# Sheet1.net
KiCad netlist of a schematic drawn in Altium Designer
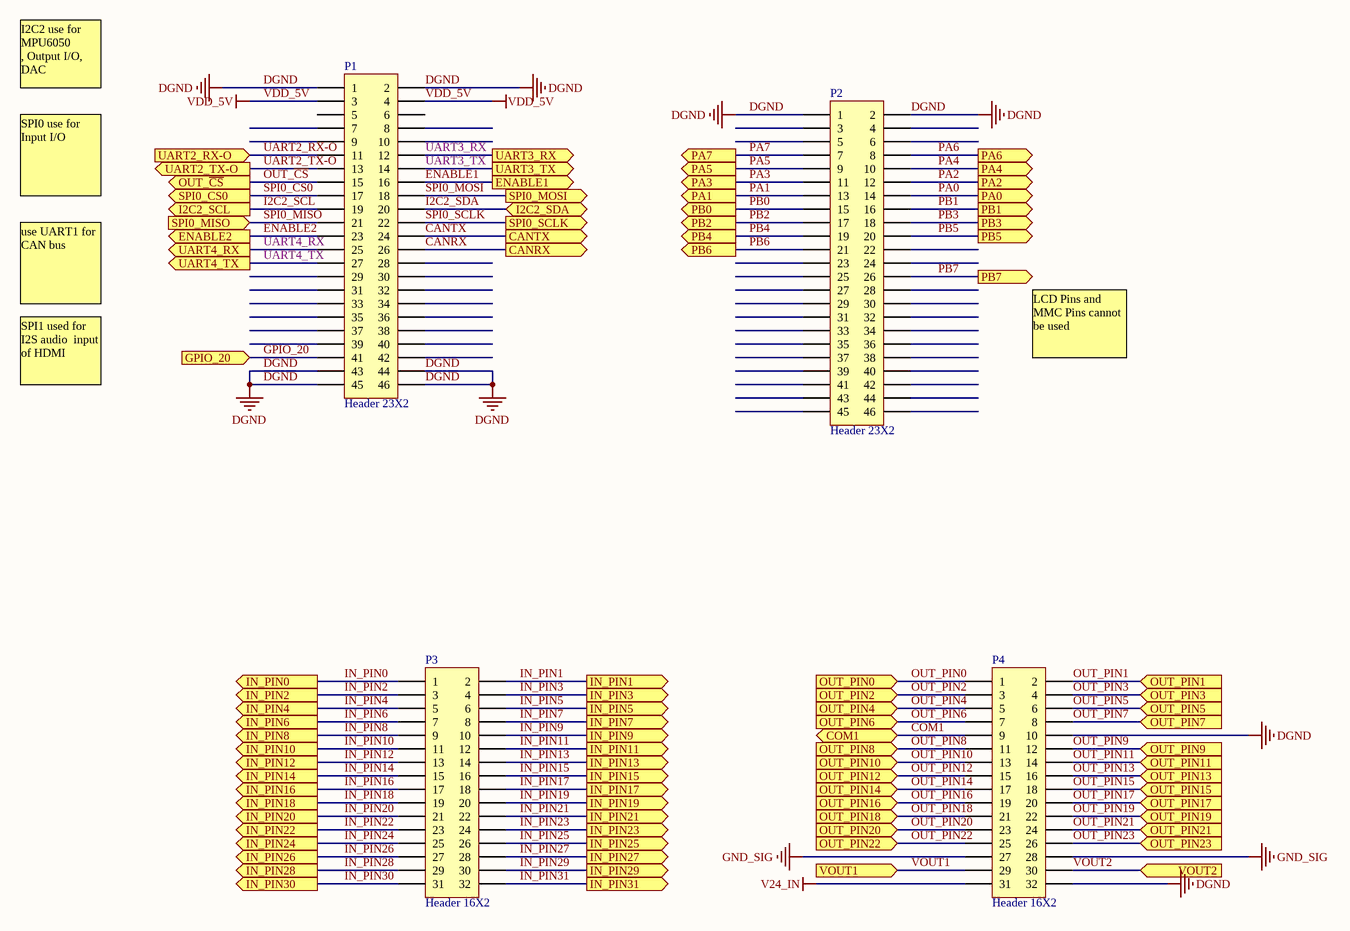
[diagram p0: Sheet1.SchDoc]

(export (version "E")
  (design (tool "Eeschema 10.0.6"))
  (components
    (comp (ref "P1")
      (value "Header 23X2")
      (footprint "HDR2X23")
      (description "Header, 23-Pin, Dual row")
      (fields (field (name "PUBLISHER") "Altium Limited"))
      (libsource (lib "dolphi_ecs") (part "Header 23X2"))
    )
    (comp (ref "P2")
      (value "Header 23X2")
      (footprint "HDR2X23")
      (description "Header, 23-Pin, Dual row")
      (fields (field (name "PUBLISHER") "Altium Limited"))
      (libsource (lib "dolphi_ecs") (part "Header 23X2"))
    )
    (comp (ref "P3")
      (value "Header 16X2")
      (footprint "CON16X2-8.5")
      (description "Header, 16-Pin, Dual row")
      (fields (field (name "PUBLISHER") "Altium Limited"))
      (libsource (lib "Miscellaneous Connectors") (part "Header 16X2"))
    )
    (comp (ref "P4")
      (value "Header 16X2")
      (footprint "CON16X2-8.5")
      (description "Header, 16-Pin, Dual row")
      (fields (field (name "PUBLISHER") "Altium Limited"))
      (libsource (lib "Miscellaneous Connectors") (part "Header 16X2"))
    )
  )
  (nets
    (net (code "1") (name "/CANRX") (class "Default")
      (node (ref "P1") (pin "26") (pinfunction "26_26") (pintype "passive"))
    )
    (net (code "2") (name "/CANTX") (class "Default")
      (node (ref "P1") (pin "24") (pinfunction "24_24") (pintype "passive"))
    )
    (net (code "3") (name "/COM1") (class "Default")
      (node (ref "P4") (pin "9") (pinfunction "9_9") (pintype "passive"))
    )
    (net (code "4") (name "/ENABLE1") (class "Default")
      (node (ref "P1") (pin "16") (pinfunction "16_16") (pintype "passive"))
    )
    (net (code "5") (name "/ENABLE2") (class "Default")
      (node (ref "P1") (pin "23") (pinfunction "23_23") (pintype "passive"))
    )
    (net (code "6") (name "/GPIO_20") (class "Default")
      (node (ref "P1") (pin "41") (pinfunction "41_41") (pintype "passive"))
    )
    (net (code "7") (name "/I2C2_SCL") (class "Default")
      (node (ref "P1") (pin "19") (pinfunction "19_19") (pintype "passive"))
    )
    (net (code "8") (name "/I2C2_SDA") (class "Default")
      (node (ref "P1") (pin "20") (pinfunction "20_20") (pintype "passive"))
    )
    (net (code "9") (name "/IN_PIN0") (class "Default")
      (node (ref "P3") (pin "1") (pinfunction "1_1") (pintype "passive"))
    )
    (net (code "10") (name "/IN_PIN1") (class "Default")
      (node (ref "P3") (pin "2") (pinfunction "2_2") (pintype "passive"))
    )
    (net (code "11") (name "/IN_PIN2") (class "Default")
      (node (ref "P3") (pin "3") (pinfunction "3_3") (pintype "passive"))
    )
    (net (code "12") (name "/IN_PIN3") (class "Default")
      (node (ref "P3") (pin "4") (pinfunction "4_4") (pintype "passive"))
    )
    (net (code "13") (name "/IN_PIN4") (class "Default")
      (node (ref "P3") (pin "5") (pinfunction "5_5") (pintype "passive"))
    )
    (net (code "14") (name "/IN_PIN5") (class "Default")
      (node (ref "P3") (pin "6") (pinfunction "6_6") (pintype "passive"))
    )
    (net (code "15") (name "/IN_PIN6") (class "Default")
      (node (ref "P3") (pin "7") (pinfunction "7_7") (pintype "passive"))
    )
    (net (code "16") (name "/IN_PIN7") (class "Default")
      (node (ref "P3") (pin "8") (pinfunction "8_8") (pintype "passive"))
    )
    (net (code "17") (name "/IN_PIN8") (class "Default")
      (node (ref "P3") (pin "9") (pinfunction "9_9") (pintype "passive"))
    )
    (net (code "18") (name "/IN_PIN9") (class "Default")
      (node (ref "P3") (pin "10") (pinfunction "10_10") (pintype "passive"))
    )
    (net (code "19") (name "/IN_PIN10") (class "Default")
      (node (ref "P3") (pin "11") (pinfunction "11_11") (pintype "passive"))
    )
    (net (code "20") (name "/IN_PIN11") (class "Default")
      (node (ref "P3") (pin "12") (pinfunction "12_12") (pintype "passive"))
    )
    (net (code "21") (name "/IN_PIN12") (class "Default")
      (node (ref "P3") (pin "13") (pinfunction "13_13") (pintype "passive"))
    )
    (net (code "22") (name "/IN_PIN13") (class "Default")
      (node (ref "P3") (pin "14") (pinfunction "14_14") (pintype "passive"))
    )
    (net (code "23") (name "/IN_PIN14") (class "Default")
      (node (ref "P3") (pin "15") (pinfunction "15_15") (pintype "passive"))
    )
    (net (code "24") (name "/IN_PIN15") (class "Default")
      (node (ref "P3") (pin "16") (pinfunction "16_16") (pintype "passive"))
    )
    (net (code "25") (name "/IN_PIN16") (class "Default")
      (node (ref "P3") (pin "17") (pinfunction "17_17") (pintype "passive"))
    )
    (net (code "26") (name "/IN_PIN17") (class "Default")
      (node (ref "P3") (pin "18") (pinfunction "18_18") (pintype "passive"))
    )
    (net (code "27") (name "/IN_PIN18") (class "Default")
      (node (ref "P3") (pin "19") (pinfunction "19_19") (pintype "passive"))
    )
    (net (code "28") (name "/IN_PIN19") (class "Default")
      (node (ref "P3") (pin "20") (pinfunction "20_20") (pintype "passive"))
    )
    (net (code "29") (name "/IN_PIN20") (class "Default")
      (node (ref "P3") (pin "21") (pinfunction "21_21") (pintype "passive"))
    )
    (net (code "30") (name "/IN_PIN21") (class "Default")
      (node (ref "P3") (pin "22") (pinfunction "22_22") (pintype "passive"))
    )
    (net (code "31") (name "/IN_PIN22") (class "Default")
      (node (ref "P3") (pin "23") (pinfunction "23_23") (pintype "passive"))
    )
    (net (code "32") (name "/IN_PIN23") (class "Default")
      (node (ref "P3") (pin "24") (pinfunction "24_24") (pintype "passive"))
    )
    (net (code "33") (name "/IN_PIN24") (class "Default")
      (node (ref "P3") (pin "25") (pinfunction "25_25") (pintype "passive"))
    )
    (net (code "34") (name "/IN_PIN25") (class "Default")
      (node (ref "P3") (pin "26") (pinfunction "26_26") (pintype "passive"))
    )
    (net (code "35") (name "/IN_PIN26") (class "Default")
      (node (ref "P3") (pin "27") (pinfunction "27_27") (pintype "passive"))
    )
    (net (code "36") (name "/IN_PIN27") (class "Default")
      (node (ref "P3") (pin "28") (pinfunction "28_28") (pintype "passive"))
    )
    (net (code "37") (name "/IN_PIN28") (class "Default")
      (node (ref "P3") (pin "29") (pinfunction "29_29") (pintype "passive"))
    )
    (net (code "38") (name "/IN_PIN29") (class "Default")
      (node (ref "P3") (pin "30") (pinfunction "30_30") (pintype "passive"))
    )
    (net (code "39") (name "/IN_PIN30") (class "Default")
      (node (ref "P3") (pin "31") (pinfunction "31_31") (pintype "passive"))
    )
    (net (code "40") (name "/IN_PIN31") (class "Default")
      (node (ref "P3") (pin "32") (pinfunction "32_32") (pintype "passive"))
    )
    (net (code "41") (name "/OUT_PIN0") (class "Default")
      (node (ref "P4") (pin "1") (pinfunction "1_1") (pintype "passive"))
    )
    (net (code "42") (name "/OUT_PIN1") (class "Default")
      (node (ref "P4") (pin "2") (pinfunction "2_2") (pintype "passive"))
    )
    (net (code "43") (name "/OUT_PIN2") (class "Default")
      (node (ref "P4") (pin "3") (pinfunction "3_3") (pintype "passive"))
    )
    (net (code "44") (name "/OUT_PIN3") (class "Default")
      (node (ref "P4") (pin "4") (pinfunction "4_4") (pintype "passive"))
    )
    (net (code "45") (name "/OUT_PIN4") (class "Default")
      (node (ref "P4") (pin "5") (pinfunction "5_5") (pintype "passive"))
    )
    (net (code "46") (name "/OUT_PIN5") (class "Default")
      (node (ref "P4") (pin "6") (pinfunction "6_6") (pintype "passive"))
    )
    (net (code "47") (name "/OUT_PIN6") (class "Default")
      (node (ref "P4") (pin "7") (pinfunction "7_7") (pintype "passive"))
    )
    (net (code "48") (name "/OUT_PIN7") (class "Default")
      (node (ref "P4") (pin "8") (pinfunction "8_8") (pintype "passive"))
    )
    (net (code "49") (name "/OUT_PIN8") (class "Default")
      (node (ref "P4") (pin "11") (pinfunction "11_11") (pintype "passive"))
    )
    (net (code "50") (name "/OUT_PIN9") (class "Default")
      (node (ref "P4") (pin "12") (pinfunction "12_12") (pintype "passive"))
    )
    (net (code "51") (name "/OUT_PIN10") (class "Default")
      (node (ref "P4") (pin "13") (pinfunction "13_13") (pintype "passive"))
    )
    (net (code "52") (name "/OUT_PIN11") (class "Default")
      (node (ref "P4") (pin "14") (pinfunction "14_14") (pintype "passive"))
    )
    (net (code "53") (name "/OUT_PIN12") (class "Default")
      (node (ref "P4") (pin "15") (pinfunction "15_15") (pintype "passive"))
    )
    (net (code "54") (name "/OUT_PIN13") (class "Default")
      (node (ref "P4") (pin "16") (pinfunction "16_16") (pintype "passive"))
    )
    (net (code "55") (name "/OUT_PIN14") (class "Default")
      (node (ref "P4") (pin "17") (pinfunction "17_17") (pintype "passive"))
    )
    (net (code "56") (name "/OUT_PIN15") (class "Default")
      (node (ref "P4") (pin "18") (pinfunction "18_18") (pintype "passive"))
    )
    (net (code "57") (name "/OUT_PIN16") (class "Default")
      (node (ref "P4") (pin "19") (pinfunction "19_19") (pintype "passive"))
    )
    (net (code "58") (name "/OUT_PIN17") (class "Default")
      (node (ref "P4") (pin "20") (pinfunction "20_20") (pintype "passive"))
    )
    (net (code "59") (name "/OUT_PIN18") (class "Default")
      (node (ref "P4") (pin "21") (pinfunction "21_21") (pintype "passive"))
    )
    (net (code "60") (name "/OUT_PIN19") (class "Default")
      (node (ref "P4") (pin "22") (pinfunction "22_22") (pintype "passive"))
    )
    (net (code "61") (name "/OUT_PIN20") (class "Default")
      (node (ref "P4") (pin "23") (pinfunction "23_23") (pintype "passive"))
    )
    (net (code "62") (name "/OUT_PIN21") (class "Default")
      (node (ref "P4") (pin "24") (pinfunction "24_24") (pintype "passive"))
    )
    (net (code "63") (name "/OUT_PIN22") (class "Default")
      (node (ref "P4") (pin "25") (pinfunction "25_25") (pintype "passive"))
    )
    (net (code "64") (name "/OUT_PIN23") (class "Default")
      (node (ref "P4") (pin "26") (pinfunction "26_26") (pintype "passive"))
    )
    (net (code "65") (name "/OUT_~{CS}") (class "Default")
      (node (ref "P1") (pin "15") (pinfunction "15_15") (pintype "passive"))
    )
    (net (code "66") (name "/PA0") (class "Default")
      (node (ref "P2") (pin "14") (pinfunction "14_14") (pintype "passive"))
    )
    (net (code "67") (name "/PA1") (class "Default")
      (node (ref "P2") (pin "13") (pinfunction "13_13") (pintype "passive"))
    )
    (net (code "68") (name "/PA2") (class "Default")
      (node (ref "P2") (pin "12") (pinfunction "12_12") (pintype "passive"))
    )
    (net (code "69") (name "/PA3") (class "Default")
      (node (ref "P2") (pin "11") (pinfunction "11_11") (pintype "passive"))
    )
    (net (code "70") (name "/PA4") (class "Default")
      (node (ref "P2") (pin "10") (pinfunction "10_10") (pintype "passive"))
    )
    (net (code "71") (name "/PA5") (class "Default")
      (node (ref "P2") (pin "9") (pinfunction "9_9") (pintype "passive"))
    )
    (net (code "72") (name "/PA6") (class "Default")
      (node (ref "P2") (pin "8") (pinfunction "8_8") (pintype "passive"))
    )
    (net (code "73") (name "/PA7") (class "Default")
      (node (ref "P2") (pin "7") (pinfunction "7_7") (pintype "passive"))
    )
    (net (code "74") (name "/PB0") (class "Default")
      (node (ref "P2") (pin "15") (pinfunction "15_15") (pintype "passive"))
    )
    (net (code "75") (name "/PB1") (class "Default")
      (node (ref "P2") (pin "16") (pinfunction "16_16") (pintype "passive"))
    )
    (net (code "76") (name "/PB2") (class "Default")
      (node (ref "P2") (pin "17") (pinfunction "17_17") (pintype "passive"))
    )
    (net (code "77") (name "/PB3") (class "Default")
      (node (ref "P2") (pin "18") (pinfunction "18_18") (pintype "passive"))
    )
    (net (code "78") (name "/PB4") (class "Default")
      (node (ref "P2") (pin "19") (pinfunction "19_19") (pintype "passive"))
    )
    (net (code "79") (name "/PB5") (class "Default")
      (node (ref "P2") (pin "20") (pinfunction "20_20") (pintype "passive"))
    )
    (net (code "80") (name "/PB6") (class "Default")
      (node (ref "P2") (pin "21") (pinfunction "21_21") (pintype "passive"))
    )
    (net (code "81") (name "/PB7") (class "Default")
      (node (ref "P2") (pin "26") (pinfunction "26_26") (pintype "passive"))
    )
    (net (code "82") (name "/SPI0_CS0") (class "Default")
      (node (ref "P1") (pin "17") (pinfunction "17_17") (pintype "passive"))
    )
    (net (code "83") (name "/SPI0_MISO") (class "Default")
      (node (ref "P1") (pin "21") (pinfunction "21_21") (pintype "passive"))
    )
    (net (code "84") (name "/SPI0_MOSI") (class "Default")
      (node (ref "P1") (pin "18") (pinfunction "18_18") (pintype "passive"))
    )
    (net (code "85") (name "/SPI0_SCLK") (class "Default")
      (node (ref "P1") (pin "22") (pinfunction "22_22") (pintype "passive"))
    )
    (net (code "86") (name "/UART2_RX-O") (class "Default")
      (node (ref "P1") (pin "11") (pinfunction "11_11") (pintype "passive"))
    )
    (net (code "87") (name "/UART2_TX-O") (class "Default")
      (node (ref "P1") (pin "13") (pinfunction "13_13") (pintype "passive"))
    )
    (net (code "88") (name "/UART3_RX") (class "Default")
      (node (ref "P1") (pin "12") (pinfunction "12_12") (pintype "passive"))
    )
    (net (code "89") (name "/UART3_TX") (class "Default")
      (node (ref "P1") (pin "14") (pinfunction "14_14") (pintype "passive"))
    )
    (net (code "90") (name "/UART4_RX") (class "Default")
      (node (ref "P1") (pin "25") (pinfunction "25_25") (pintype "passive"))
    )
    (net (code "91") (name "/UART4_TX") (class "Default")
      (node (ref "P1") (pin "27") (pinfunction "27_27") (pintype "passive"))
    )
    (net (code "92") (name "/VOUT1") (class "Default")
      (node (ref "P4") (pin "29") (pinfunction "29_29") (pintype "passive"))
    )
    (net (code "93") (name "/VOUT2") (class "Default")
      (node (ref "P4") (pin "30") (pinfunction "30_30") (pintype "passive"))
    )
    (net (code "94") (name "DGND") (class "Default")
      (node (ref "P1") (pin "1") (pinfunction "1_1") (pintype "passive"))
      (node (ref "P1") (pin "2") (pinfunction "2_2") (pintype "passive"))
      (node (ref "P1") (pin "43") (pinfunction "43_43") (pintype "passive"))
      (node (ref "P1") (pin "44") (pinfunction "44_44") (pintype "passive"))
      (node (ref "P1") (pin "45") (pinfunction "45_45") (pintype "passive"))
      (node (ref "P1") (pin "46") (pinfunction "46_46") (pintype "passive"))
      (node (ref "P2") (pin "1") (pinfunction "1_1") (pintype "passive"))
      (node (ref "P2") (pin "2") (pinfunction "2_2") (pintype "passive"))
      (node (ref "P4") (pin "10") (pinfunction "10_10") (pintype "passive"))
      (node (ref "P4") (pin "32") (pinfunction "32_32") (pintype "passive"))
    )
    (net (code "95") (name "GND_SIG") (class "Default")
      (node (ref "P4") (pin "27") (pinfunction "27_27") (pintype "passive"))
      (node (ref "P4") (pin "28") (pinfunction "28_28") (pintype "passive"))
    )
    (net (code "96") (name "V24_IN") (class "Default")
      (node (ref "P4") (pin "31") (pinfunction "31_31") (pintype "passive"))
    )
    (net (code "97") (name "VDD_5V") (class "Default")
      (node (ref "P1") (pin "3") (pinfunction "3_3") (pintype "passive"))
      (node (ref "P1") (pin "4") (pinfunction "4_4") (pintype "passive"))
    )
    (net (code "98") (name "unconnected-(P1-Pad5)") (class "Default")
      (node (ref "P1") (pin "5") (pinfunction "5_5") (pintype "passive"))
    )
    (net (code "99") (name "unconnected-(P1-Pad6)") (class "Default")
      (node (ref "P1") (pin "6") (pinfunction "6_6") (pintype "passive"))
    )
    (net (code "100") (name "unconnected-(P1-Pad7)") (class "Default")
      (node (ref "P1") (pin "7") (pinfunction "7_7") (pintype "passive"))
    )
    (net (code "101") (name "unconnected-(P1-Pad8)") (class "Default")
      (node (ref "P1") (pin "8") (pinfunction "8_8") (pintype "passive"))
    )
    (net (code "102") (name "unconnected-(P1-Pad9)") (class "Default")
      (node (ref "P1") (pin "9") (pinfunction "9_9") (pintype "passive"))
    )
    (net (code "103") (name "unconnected-(P1-Pad10)") (class "Default")
      (node (ref "P1") (pin "10") (pinfunction "10_10") (pintype "passive"))
    )
    (net (code "104") (name "unconnected-(P1-Pad28)") (class "Default")
      (node (ref "P1") (pin "28") (pinfunction "28_28") (pintype "passive"))
    )
    (net (code "105") (name "unconnected-(P1-Pad29)") (class "Default")
      (node (ref "P1") (pin "29") (pinfunction "29_29") (pintype "passive"))
    )
    (net (code "106") (name "unconnected-(P1-Pad30)") (class "Default")
      (node (ref "P1") (pin "30") (pinfunction "30_30") (pintype "passive"))
    )
    (net (code "107") (name "unconnected-(P1-Pad31)") (class "Default")
      (node (ref "P1") (pin "31") (pinfunction "31_31") (pintype "passive"))
    )
    (net (code "108") (name "unconnected-(P1-Pad32)") (class "Default")
      (node (ref "P1") (pin "32") (pinfunction "32_32") (pintype "passive"))
    )
    (net (code "109") (name "unconnected-(P1-Pad33)") (class "Default")
      (node (ref "P1") (pin "33") (pinfunction "33_33") (pintype "passive"))
    )
    (net (code "110") (name "unconnected-(P1-Pad34)") (class "Default")
      (node (ref "P1") (pin "34") (pinfunction "34_34") (pintype "passive"))
    )
    (net (code "111") (name "unconnected-(P1-Pad35)") (class "Default")
      (node (ref "P1") (pin "35") (pinfunction "35_35") (pintype "passive"))
    )
    (net (code "112") (name "unconnected-(P1-Pad36)") (class "Default")
      (node (ref "P1") (pin "36") (pinfunction "36_36") (pintype "passive"))
    )
    (net (code "113") (name "unconnected-(P1-Pad37)") (class "Default")
      (node (ref "P1") (pin "37") (pinfunction "37_37") (pintype "passive"))
    )
    (net (code "114") (name "unconnected-(P1-Pad38)") (class "Default")
      (node (ref "P1") (pin "38") (pinfunction "38_38") (pintype "passive"))
    )
    (net (code "115") (name "unconnected-(P1-Pad39)") (class "Default")
      (node (ref "P1") (pin "39") (pinfunction "39_39") (pintype "passive"))
    )
    (net (code "116") (name "unconnected-(P1-Pad40)") (class "Default")
      (node (ref "P1") (pin "40") (pinfunction "40_40") (pintype "passive"))
    )
    (net (code "117") (name "unconnected-(P1-Pad42)") (class "Default")
      (node (ref "P1") (pin "42") (pinfunction "42_42") (pintype "passive"))
    )
    (net (code "118") (name "unconnected-(P2-Pad3)") (class "Default")
      (node (ref "P2") (pin "3") (pinfunction "3_3") (pintype "passive"))
    )
    (net (code "119") (name "unconnected-(P2-Pad4)") (class "Default")
      (node (ref "P2") (pin "4") (pinfunction "4_4") (pintype "passive"))
    )
    (net (code "120") (name "unconnected-(P2-Pad5)") (class "Default")
      (node (ref "P2") (pin "5") (pinfunction "5_5") (pintype "passive"))
    )
    (net (code "121") (name "unconnected-(P2-Pad6)") (class "Default")
      (node (ref "P2") (pin "6") (pinfunction "6_6") (pintype "passive"))
    )
    (net (code "122") (name "unconnected-(P2-Pad22)") (class "Default")
      (node (ref "P2") (pin "22") (pinfunction "22_22") (pintype "passive"))
    )
    (net (code "123") (name "unconnected-(P2-Pad23)") (class "Default")
      (node (ref "P2") (pin "23") (pinfunction "23_23") (pintype "passive"))
    )
    (net (code "124") (name "unconnected-(P2-Pad24)") (class "Default")
      (node (ref "P2") (pin "24") (pinfunction "24_24") (pintype "passive"))
    )
    (net (code "125") (name "unconnected-(P2-Pad25)") (class "Default")
      (node (ref "P2") (pin "25") (pinfunction "25_25") (pintype "passive"))
    )
    (net (code "126") (name "unconnected-(P2-Pad27)") (class "Default")
      (node (ref "P2") (pin "27") (pinfunction "27_27") (pintype "passive"))
    )
    (net (code "127") (name "unconnected-(P2-Pad28)") (class "Default")
      (node (ref "P2") (pin "28") (pinfunction "28_28") (pintype "passive"))
    )
    (net (code "128") (name "unconnected-(P2-Pad29)") (class "Default")
      (node (ref "P2") (pin "29") (pinfunction "29_29") (pintype "passive"))
    )
    (net (code "129") (name "unconnected-(P2-Pad30)") (class "Default")
      (node (ref "P2") (pin "30") (pinfunction "30_30") (pintype "passive"))
    )
    (net (code "130") (name "unconnected-(P2-Pad31)") (class "Default")
      (node (ref "P2") (pin "31") (pinfunction "31_31") (pintype "passive"))
    )
    (net (code "131") (name "unconnected-(P2-Pad32)") (class "Default")
      (node (ref "P2") (pin "32") (pinfunction "32_32") (pintype "passive"))
    )
    (net (code "132") (name "unconnected-(P2-Pad33)") (class "Default")
      (node (ref "P2") (pin "33") (pinfunction "33_33") (pintype "passive"))
    )
    (net (code "133") (name "unconnected-(P2-Pad34)") (class "Default")
      (node (ref "P2") (pin "34") (pinfunction "34_34") (pintype "passive"))
    )
    (net (code "134") (name "unconnected-(P2-Pad35)") (class "Default")
      (node (ref "P2") (pin "35") (pinfunction "35_35") (pintype "passive"))
    )
    (net (code "135") (name "unconnected-(P2-Pad36)") (class "Default")
      (node (ref "P2") (pin "36") (pinfunction "36_36") (pintype "passive"))
    )
    (net (code "136") (name "unconnected-(P2-Pad37)") (class "Default")
      (node (ref "P2") (pin "37") (pinfunction "37_37") (pintype "passive"))
    )
    (net (code "137") (name "unconnected-(P2-Pad38)") (class "Default")
      (node (ref "P2") (pin "38") (pinfunction "38_38") (pintype "passive"))
    )
    (net (code "138") (name "unconnected-(P2-Pad39)") (class "Default")
      (node (ref "P2") (pin "39") (pinfunction "39_39") (pintype "passive"))
    )
    (net (code "139") (name "unconnected-(P2-Pad40)") (class "Default")
      (node (ref "P2") (pin "40") (pinfunction "40_40") (pintype "passive"))
    )
    (net (code "140") (name "unconnected-(P2-Pad41)") (class "Default")
      (node (ref "P2") (pin "41") (pinfunction "41_41") (pintype "passive"))
    )
    (net (code "141") (name "unconnected-(P2-Pad42)") (class "Default")
      (node (ref "P2") (pin "42") (pinfunction "42_42") (pintype "passive"))
    )
    (net (code "142") (name "unconnected-(P2-Pad43)") (class "Default")
      (node (ref "P2") (pin "43") (pinfunction "43_43") (pintype "passive"))
    )
    (net (code "143") (name "unconnected-(P2-Pad44)") (class "Default")
      (node (ref "P2") (pin "44") (pinfunction "44_44") (pintype "passive"))
    )
    (net (code "144") (name "unconnected-(P2-Pad45)") (class "Default")
      (node (ref "P2") (pin "45") (pinfunction "45_45") (pintype "passive"))
    )
    (net (code "145") (name "unconnected-(P2-Pad46)") (class "Default")
      (node (ref "P2") (pin "46") (pinfunction "46_46") (pintype "passive"))
    )
  )
)
